# Batt_Op_Amp.net
KiCad netlist of a schematic drawn in Altium Designer
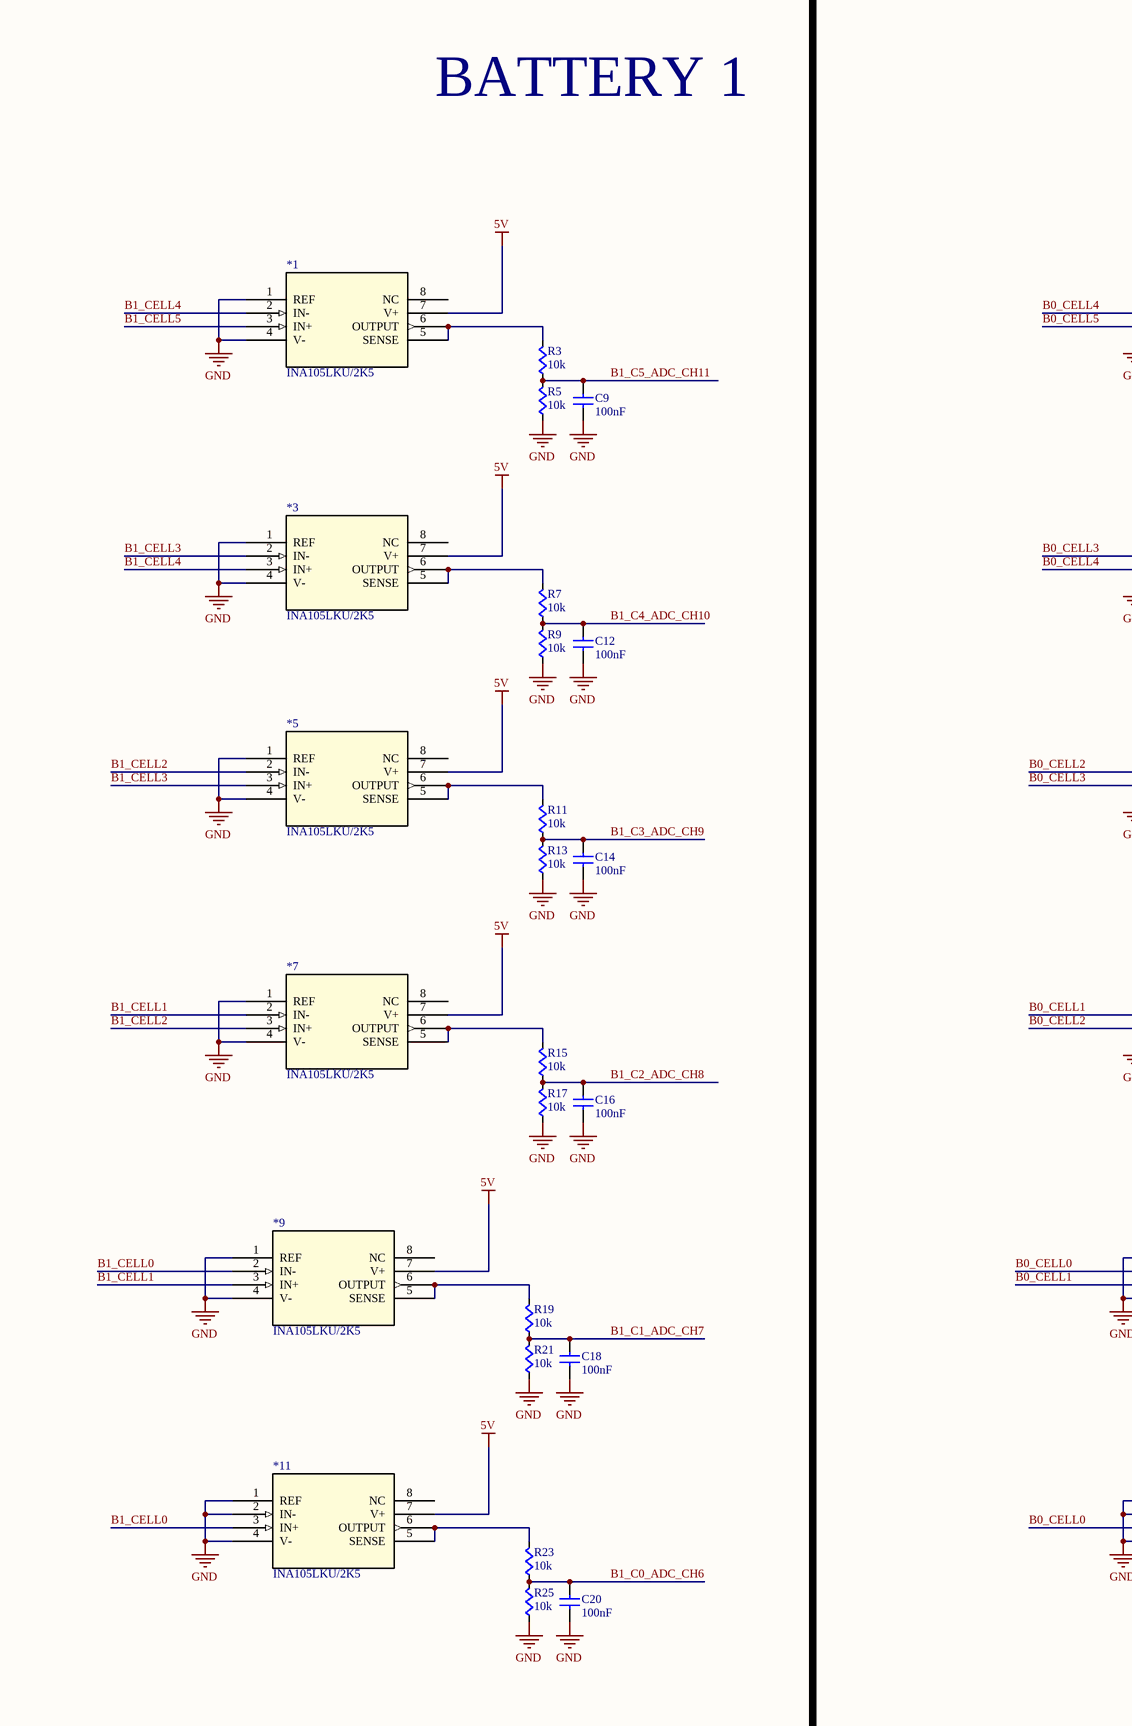
[diagram p0: Batt_Op_Amp.SchDoc, left]
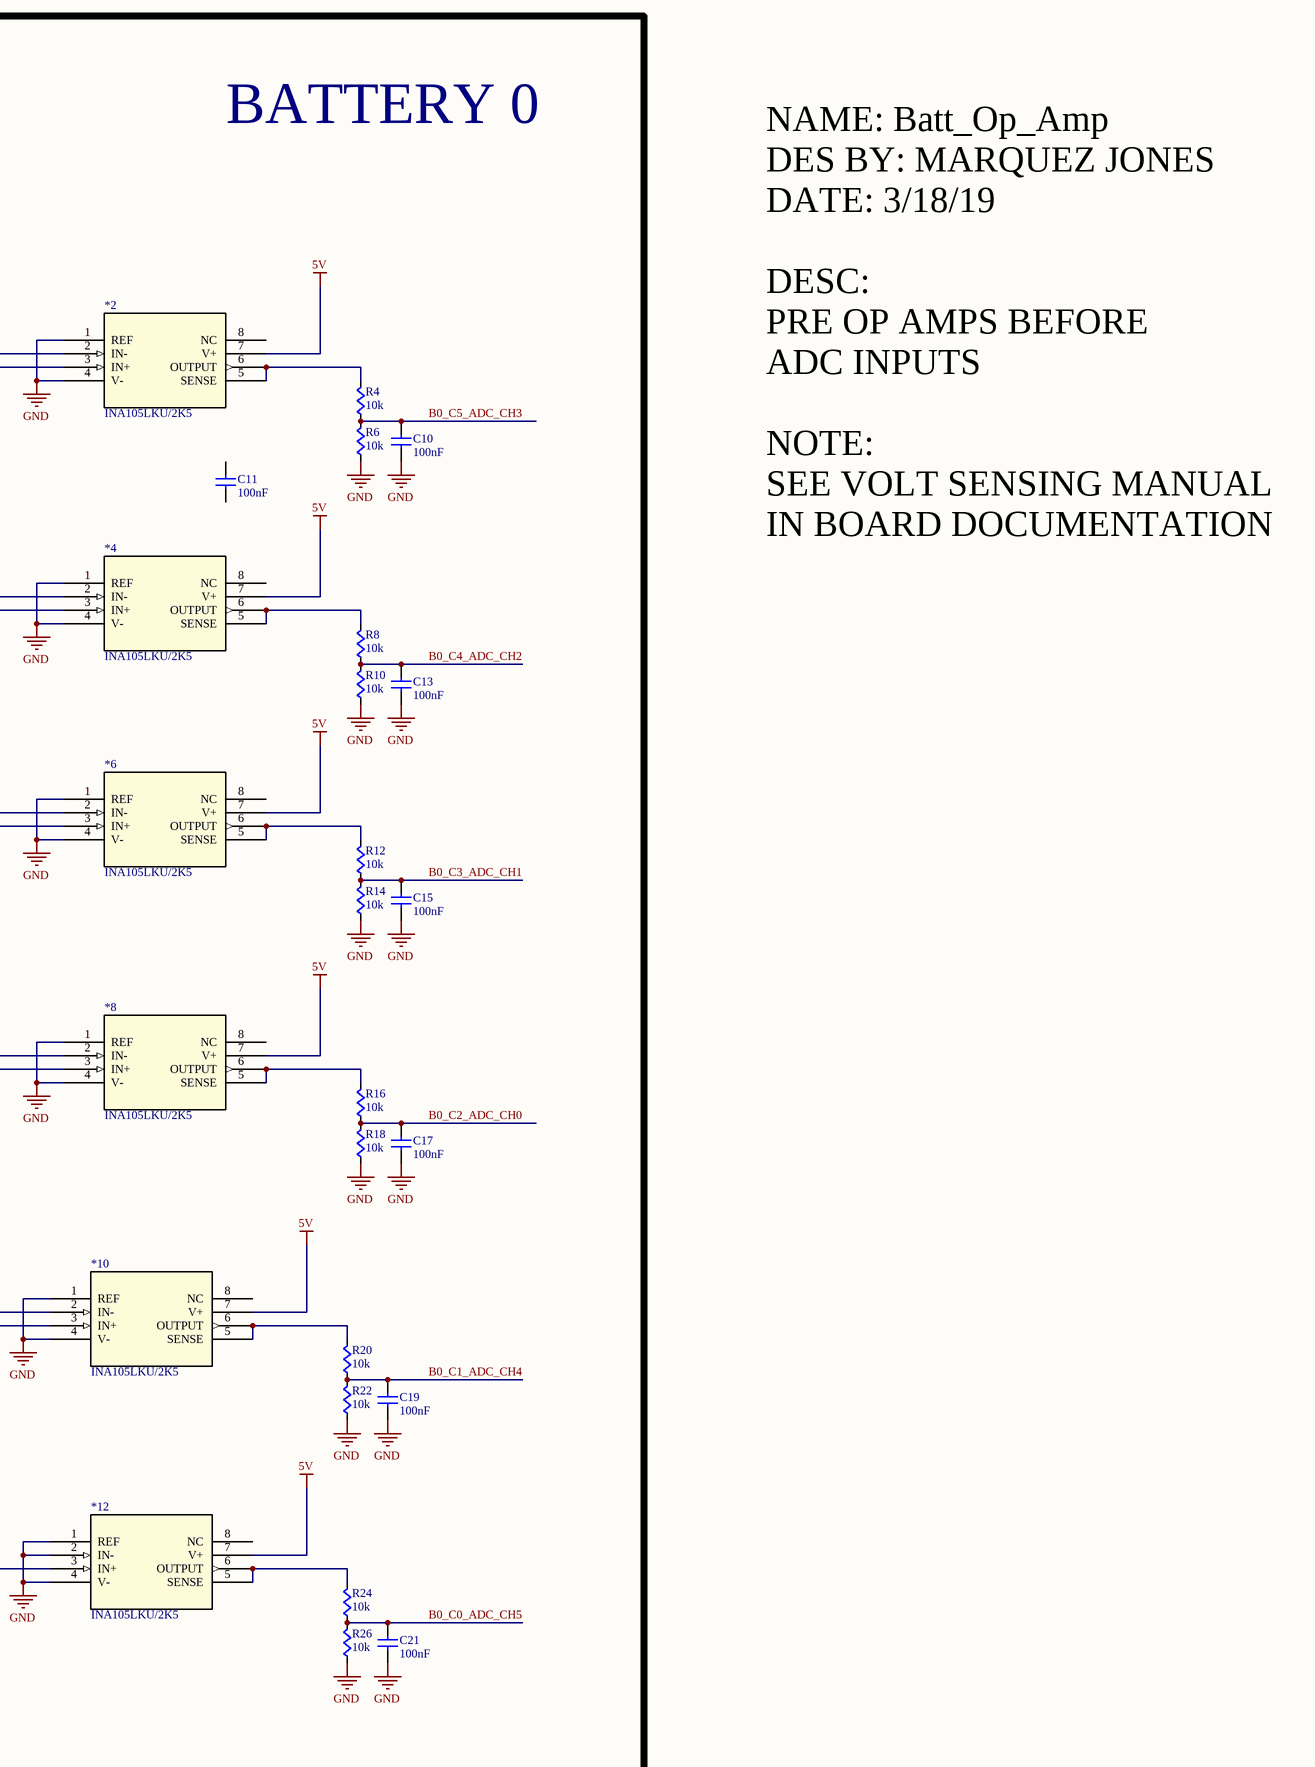
[diagram p1: Batt_Op_Amp.SchDoc, right]

(export (version "E")
  (design (tool "Eeschema 10.0.6"))
  (components
    (comp (ref "*1")
      (value "INA105LKU/2K5")
      (footprint "SOIC-8N")
      (libsource (lib "ICs") (part "INA105LKU/2K5"))
    )
    (comp (ref "*2")
      (value "INA105LKU/2K5")
      (footprint "SOIC-8N")
      (libsource (lib "ICs") (part "INA105LKU/2K5"))
    )
    (comp (ref "*3")
      (value "INA105LKU/2K5")
      (footprint "SOIC-8N")
      (libsource (lib "ICs") (part "INA105LKU/2K5"))
    )
    (comp (ref "*4")
      (value "INA105LKU/2K5")
      (footprint "SOIC-8N")
      (libsource (lib "ICs") (part "INA105LKU/2K5"))
    )
    (comp (ref "*5")
      (value "INA105LKU/2K5")
      (footprint "SOIC-8N")
      (libsource (lib "ICs") (part "INA105LKU/2K5"))
    )
    (comp (ref "*6")
      (value "INA105LKU/2K5")
      (footprint "SOIC-8N")
      (libsource (lib "ICs") (part "INA105LKU/2K5"))
    )
    (comp (ref "*7")
      (value "INA105LKU/2K5")
      (footprint "SOIC-8N")
      (libsource (lib "ICs") (part "INA105LKU/2K5"))
    )
    (comp (ref "*8")
      (value "INA105LKU/2K5")
      (footprint "SOIC-8N")
      (libsource (lib "ICs") (part "INA105LKU/2K5"))
    )
    (comp (ref "*9")
      (value "INA105LKU/2K5")
      (footprint "SOIC-8N")
      (libsource (lib "ICs") (part "INA105LKU/2K5"))
    )
    (comp (ref "*10")
      (value "INA105LKU/2K5")
      (footprint "SOIC-8N")
      (libsource (lib "ICs") (part "INA105LKU/2K5"))
    )
    (comp (ref "*11")
      (value "INA105LKU/2K5")
      (footprint "SOIC-8N")
      (libsource (lib "ICs") (part "INA105LKU/2K5"))
    )
    (comp (ref "*12")
      (value "INA105LKU/2K5")
      (footprint "SOIC-8N")
      (libsource (lib "ICs") (part "INA105LKU/2K5"))
    )
    (comp (ref "C9")
      (value "100nF")
      (footprint "CAPC0603")
      (fields (field (name "Comment") "Cap"))
      (libsource (lib "Passives") (part "Cap"))
    )
    (comp (ref "C10")
      (value "100nF")
      (footprint "CAPC0603")
      (fields (field (name "Comment") "Cap"))
      (libsource (lib "Passives") (part "Cap"))
    )
    (comp (ref "C11")
      (value "100nF")
      (footprint "CAPC0603")
      (fields (field (name "Comment") "Cap"))
      (libsource (lib "Passives") (part "Cap"))
    )
    (comp (ref "C12")
      (value "100nF")
      (footprint "CAPC0603")
      (fields (field (name "Comment") "Cap"))
      (libsource (lib "Passives") (part "Cap"))
    )
    (comp (ref "C13")
      (value "100nF")
      (footprint "CAPC0603")
      (fields (field (name "Comment") "Cap"))
      (libsource (lib "Passives") (part "Cap"))
    )
    (comp (ref "C14")
      (value "100nF")
      (footprint "CAPC0603")
      (fields (field (name "Comment") "Cap"))
      (libsource (lib "Passives") (part "Cap"))
    )
    (comp (ref "C15")
      (value "100nF")
      (footprint "CAPC0603")
      (fields (field (name "Comment") "Cap"))
      (libsource (lib "Passives") (part "Cap"))
    )
    (comp (ref "C16")
      (value "100nF")
      (footprint "CAPC0603")
      (fields (field (name "Comment") "Cap"))
      (libsource (lib "Passives") (part "Cap"))
    )
    (comp (ref "C17")
      (value "100nF")
      (footprint "CAPC0603")
      (fields (field (name "Comment") "Cap"))
      (libsource (lib "Passives") (part "Cap"))
    )
    (comp (ref "C18")
      (value "100nF")
      (footprint "CAPC0603")
      (fields (field (name "Comment") "Cap"))
      (libsource (lib "Passives") (part "Cap"))
    )
    (comp (ref "C19")
      (value "100nF")
      (footprint "CAPC0603")
      (fields (field (name "Comment") "Cap"))
      (libsource (lib "Passives") (part "Cap"))
    )
    (comp (ref "C20")
      (value "100nF")
      (footprint "CAPC0603")
      (fields (field (name "Comment") "Cap"))
      (libsource (lib "Passives") (part "Cap"))
    )
    (comp (ref "C21")
      (value "100nF")
      (footprint "CAPC0603")
      (fields (field (name "Comment") "Cap"))
      (libsource (lib "Passives") (part "Cap"))
    )
    (comp (ref "R3")
      (value "10k")
      (footprint "WSLP5931")
      (fields (field (name "Comment") "Res"))
      (libsource (lib "Passives") (part "Res"))
    )
    (comp (ref "R4")
      (value "10k")
      (footprint "WSLP5931")
      (fields (field (name "Comment") "Res"))
      (libsource (lib "Passives") (part "Res"))
    )
    (comp (ref "R5")
      (value "10k")
      (footprint "WSLP5931")
      (fields (field (name "Comment") "Res"))
      (libsource (lib "Passives") (part "Res"))
    )
    (comp (ref "R6")
      (value "10k")
      (footprint "WSLP5931")
      (fields (field (name "Comment") "Res"))
      (libsource (lib "Passives") (part "Res"))
    )
    (comp (ref "R7")
      (value "10k")
      (footprint "WSLP5931")
      (fields (field (name "Comment") "Res"))
      (libsource (lib "Passives") (part "Res"))
    )
    (comp (ref "R8")
      (value "10k")
      (footprint "WSLP5931")
      (fields (field (name "Comment") "Res"))
      (libsource (lib "Passives") (part "Res"))
    )
    (comp (ref "R9")
      (value "10k")
      (footprint "WSLP5931")
      (fields (field (name "Comment") "Res"))
      (libsource (lib "Passives") (part "Res"))
    )
    (comp (ref "R10")
      (value "10k")
      (footprint "WSLP5931")
      (fields (field (name "Comment") "Res"))
      (libsource (lib "Passives") (part "Res"))
    )
    (comp (ref "R11")
      (value "10k")
      (footprint "WSLP5931")
      (fields (field (name "Comment") "Res"))
      (libsource (lib "Passives") (part "Res"))
    )
    (comp (ref "R12")
      (value "10k")
      (footprint "WSLP5931")
      (fields (field (name "Comment") "Res"))
      (libsource (lib "Passives") (part "Res"))
    )
    (comp (ref "R13")
      (value "10k")
      (footprint "WSLP5931")
      (fields (field (name "Comment") "Res"))
      (libsource (lib "Passives") (part "Res"))
    )
    (comp (ref "R14")
      (value "10k")
      (footprint "WSLP5931")
      (fields (field (name "Comment") "Res"))
      (libsource (lib "Passives") (part "Res"))
    )
    (comp (ref "R15")
      (value "10k")
      (footprint "WSLP5931")
      (fields (field (name "Comment") "Res"))
      (libsource (lib "Passives") (part "Res"))
    )
    (comp (ref "R16")
      (value "10k")
      (footprint "WSLP5931")
      (fields (field (name "Comment") "Res"))
      (libsource (lib "Passives") (part "Res"))
    )
    (comp (ref "R17")
      (value "10k")
      (footprint "WSLP5931")
      (fields (field (name "Comment") "Res"))
      (libsource (lib "Passives") (part "Res"))
    )
    (comp (ref "R18")
      (value "10k")
      (footprint "WSLP5931")
      (fields (field (name "Comment") "Res"))
      (libsource (lib "Passives") (part "Res"))
    )
    (comp (ref "R19")
      (value "10k")
      (footprint "WSLP5931")
      (fields (field (name "Comment") "Res"))
      (libsource (lib "Passives") (part "Res"))
    )
    (comp (ref "R20")
      (value "10k")
      (footprint "WSLP5931")
      (fields (field (name "Comment") "Res"))
      (libsource (lib "Passives") (part "Res"))
    )
    (comp (ref "R21")
      (value "10k")
      (footprint "WSLP5931")
      (fields (field (name "Comment") "Res"))
      (libsource (lib "Passives") (part "Res"))
    )
    (comp (ref "R22")
      (value "10k")
      (footprint "WSLP5931")
      (fields (field (name "Comment") "Res"))
      (libsource (lib "Passives") (part "Res"))
    )
    (comp (ref "R23")
      (value "10k")
      (footprint "WSLP5931")
      (fields (field (name "Comment") "Res"))
      (libsource (lib "Passives") (part "Res"))
    )
    (comp (ref "R24")
      (value "10k")
      (footprint "WSLP5931")
      (fields (field (name "Comment") "Res"))
      (libsource (lib "Passives") (part "Res"))
    )
    (comp (ref "R25")
      (value "10k")
      (footprint "WSLP5931")
      (fields (field (name "Comment") "Res"))
      (libsource (lib "Passives") (part "Res"))
    )
    (comp (ref "R26")
      (value "10k")
      (footprint "WSLP5931")
      (fields (field (name "Comment") "Res"))
      (libsource (lib "Passives") (part "Res"))
    )
  )
  (nets
    (net (code "1") (name "/B0_C0_ADC_CH5") (class "Default")
      (node (ref "C21") (pin "1") (pinfunction "A_1") (pintype "passive"))
      (node (ref "R24") (pin "2") (pinfunction "B_2") (pintype "passive"))
      (node (ref "R26") (pin "1") (pinfunction "A_1") (pintype "passive"))
    )
    (net (code "2") (name "/B0_C1_ADC_CH4") (class "Default")
      (node (ref "C19") (pin "1") (pinfunction "A_1") (pintype "passive"))
      (node (ref "R20") (pin "2") (pinfunction "B_2") (pintype "passive"))
      (node (ref "R22") (pin "1") (pinfunction "A_1") (pintype "passive"))
    )
    (net (code "3") (name "/B0_C2_ADC_CH0") (class "Default")
      (node (ref "C17") (pin "1") (pinfunction "A_1") (pintype "passive"))
      (node (ref "R16") (pin "2") (pinfunction "B_2") (pintype "passive"))
      (node (ref "R18") (pin "1") (pinfunction "A_1") (pintype "passive"))
    )
    (net (code "4") (name "/B0_C3_ADC_CH1") (class "Default")
      (node (ref "C15") (pin "1") (pinfunction "A_1") (pintype "passive"))
      (node (ref "R12") (pin "2") (pinfunction "B_2") (pintype "passive"))
      (node (ref "R14") (pin "1") (pinfunction "A_1") (pintype "passive"))
    )
    (net (code "5") (name "/B0_C4_ADC_CH2") (class "Default")
      (node (ref "C13") (pin "1") (pinfunction "A_1") (pintype "passive"))
      (node (ref "R10") (pin "1") (pinfunction "A_1") (pintype "passive"))
      (node (ref "R8") (pin "2") (pinfunction "B_2") (pintype "passive"))
    )
    (net (code "6") (name "/B0_C5_ADC_CH3") (class "Default")
      (node (ref "C10") (pin "1") (pinfunction "A_1") (pintype "passive"))
      (node (ref "R4") (pin "2") (pinfunction "B_2") (pintype "passive"))
      (node (ref "R6") (pin "1") (pinfunction "A_1") (pintype "passive"))
    )
    (net (code "7") (name "/B0_CELL0") (class "Default")
      (node (ref "*10") (pin "2") (pinfunction "IN-_2") (pintype "input"))
      (node (ref "*12") (pin "3") (pinfunction "IN+_3") (pintype "input"))
    )
    (net (code "8") (name "/B0_CELL1") (class "Default")
      (node (ref "*10") (pin "3") (pinfunction "IN+_3") (pintype "input"))
      (node (ref "*8") (pin "2") (pinfunction "IN-_2") (pintype "input"))
    )
    (net (code "9") (name "/B0_CELL2") (class "Default")
      (node (ref "*6") (pin "2") (pinfunction "IN-_2") (pintype "input"))
      (node (ref "*8") (pin "3") (pinfunction "IN+_3") (pintype "input"))
    )
    (net (code "10") (name "/B0_CELL3") (class "Default")
      (node (ref "*4") (pin "2") (pinfunction "IN-_2") (pintype "input"))
      (node (ref "*6") (pin "3") (pinfunction "IN+_3") (pintype "input"))
    )
    (net (code "11") (name "/B0_CELL4") (class "Default")
      (node (ref "*2") (pin "2") (pinfunction "IN-_2") (pintype "input"))
      (node (ref "*4") (pin "3") (pinfunction "IN+_3") (pintype "input"))
    )
    (net (code "12") (name "/B0_CELL5") (class "Default")
      (node (ref "*2") (pin "3") (pinfunction "IN+_3") (pintype "input"))
    )
    (net (code "13") (name "/B1_C0_ADC_CH6") (class "Default")
      (node (ref "C20") (pin "1") (pinfunction "A_1") (pintype "passive"))
      (node (ref "R23") (pin "2") (pinfunction "B_2") (pintype "passive"))
      (node (ref "R25") (pin "1") (pinfunction "A_1") (pintype "passive"))
    )
    (net (code "14") (name "/B1_C1_ADC_CH7") (class "Default")
      (node (ref "C18") (pin "1") (pinfunction "A_1") (pintype "passive"))
      (node (ref "R19") (pin "2") (pinfunction "B_2") (pintype "passive"))
      (node (ref "R21") (pin "1") (pinfunction "A_1") (pintype "passive"))
    )
    (net (code "15") (name "/B1_C2_ADC_CH8") (class "Default")
      (node (ref "C16") (pin "1") (pinfunction "A_1") (pintype "passive"))
      (node (ref "R15") (pin "2") (pinfunction "B_2") (pintype "passive"))
      (node (ref "R17") (pin "1") (pinfunction "A_1") (pintype "passive"))
    )
    (net (code "16") (name "/B1_C3_ADC_CH9") (class "Default")
      (node (ref "C14") (pin "1") (pinfunction "A_1") (pintype "passive"))
      (node (ref "R11") (pin "2") (pinfunction "B_2") (pintype "passive"))
      (node (ref "R13") (pin "1") (pinfunction "A_1") (pintype "passive"))
    )
    (net (code "17") (name "/B1_C4_ADC_CH10") (class "Default")
      (node (ref "C12") (pin "1") (pinfunction "A_1") (pintype "passive"))
      (node (ref "R7") (pin "2") (pinfunction "B_2") (pintype "passive"))
      (node (ref "R9") (pin "1") (pinfunction "A_1") (pintype "passive"))
    )
    (net (code "18") (name "/B1_C5_ADC_CH11") (class "Default")
      (node (ref "C9") (pin "1") (pinfunction "A_1") (pintype "passive"))
      (node (ref "R3") (pin "2") (pinfunction "B_2") (pintype "passive"))
      (node (ref "R5") (pin "1") (pinfunction "A_1") (pintype "passive"))
    )
    (net (code "19") (name "/B1_CELL0") (class "Default")
      (node (ref "*11") (pin "3") (pinfunction "IN+_3") (pintype "input"))
      (node (ref "*9") (pin "2") (pinfunction "IN-_2") (pintype "input"))
    )
    (net (code "20") (name "/B1_CELL1") (class "Default")
      (node (ref "*7") (pin "2") (pinfunction "IN-_2") (pintype "input"))
      (node (ref "*9") (pin "3") (pinfunction "IN+_3") (pintype "input"))
    )
    (net (code "21") (name "/B1_CELL2") (class "Default")
      (node (ref "*5") (pin "2") (pinfunction "IN-_2") (pintype "input"))
      (node (ref "*7") (pin "3") (pinfunction "IN+_3") (pintype "input"))
    )
    (net (code "22") (name "/B1_CELL3") (class "Default")
      (node (ref "*3") (pin "2") (pinfunction "IN-_2") (pintype "input"))
      (node (ref "*5") (pin "3") (pinfunction "IN+_3") (pintype "input"))
    )
    (net (code "23") (name "/B1_CELL4") (class "Default")
      (node (ref "*1") (pin "2") (pinfunction "IN-_2") (pintype "input"))
      (node (ref "*3") (pin "3") (pinfunction "IN+_3") (pintype "input"))
    )
    (net (code "24") (name "/B1_CELL5") (class "Default")
      (node (ref "*1") (pin "3") (pinfunction "IN+_3") (pintype "input"))
    )
    (net (code "25") (name "5V") (class "Default")
      (node (ref "*1") (pin "7") (pinfunction "V+_7") (pintype "power_in"))
      (node (ref "*10") (pin "7") (pinfunction "V+_7") (pintype "power_in"))
      (node (ref "*11") (pin "7") (pinfunction "V+_7") (pintype "power_in"))
      (node (ref "*12") (pin "7") (pinfunction "V+_7") (pintype "power_in"))
      (node (ref "*2") (pin "7") (pinfunction "V+_7") (pintype "power_in"))
      (node (ref "*3") (pin "7") (pinfunction "V+_7") (pintype "power_in"))
      (node (ref "*4") (pin "7") (pinfunction "V+_7") (pintype "power_in"))
      (node (ref "*5") (pin "7") (pinfunction "V+_7") (pintype "power_in"))
      (node (ref "*6") (pin "7") (pinfunction "V+_7") (pintype "power_in"))
      (node (ref "*7") (pin "7") (pinfunction "V+_7") (pintype "power_in"))
      (node (ref "*8") (pin "7") (pinfunction "V+_7") (pintype "power_in"))
      (node (ref "*9") (pin "7") (pinfunction "V+_7") (pintype "power_in"))
    )
    (net (code "26") (name "GND") (class "Default")
      (node (ref "*1") (pin "1") (pinfunction "REF_1") (pintype "power_in"))
      (node (ref "*1") (pin "4") (pinfunction "V-_4") (pintype "power_in"))
      (node (ref "*10") (pin "1") (pinfunction "REF_1") (pintype "power_in"))
      (node (ref "*10") (pin "4") (pinfunction "V-_4") (pintype "power_in"))
      (node (ref "*11") (pin "1") (pinfunction "REF_1") (pintype "power_in"))
      (node (ref "*11") (pin "2") (pinfunction "IN-_2") (pintype "input"))
      (node (ref "*11") (pin "4") (pinfunction "V-_4") (pintype "power_in"))
      (node (ref "*12") (pin "1") (pinfunction "REF_1") (pintype "power_in"))
      (node (ref "*12") (pin "2") (pinfunction "IN-_2") (pintype "input"))
      (node (ref "*12") (pin "4") (pinfunction "V-_4") (pintype "power_in"))
      (node (ref "*2") (pin "1") (pinfunction "REF_1") (pintype "power_in"))
      (node (ref "*2") (pin "4") (pinfunction "V-_4") (pintype "power_in"))
      (node (ref "*3") (pin "1") (pinfunction "REF_1") (pintype "power_in"))
      (node (ref "*3") (pin "4") (pinfunction "V-_4") (pintype "power_in"))
      (node (ref "*4") (pin "1") (pinfunction "REF_1") (pintype "power_in"))
      (node (ref "*4") (pin "4") (pinfunction "V-_4") (pintype "power_in"))
      (node (ref "*5") (pin "1") (pinfunction "REF_1") (pintype "power_in"))
      (node (ref "*5") (pin "4") (pinfunction "V-_4") (pintype "power_in"))
      (node (ref "*6") (pin "1") (pinfunction "REF_1") (pintype "power_in"))
      (node (ref "*6") (pin "4") (pinfunction "V-_4") (pintype "power_in"))
      (node (ref "*7") (pin "1") (pinfunction "REF_1") (pintype "power_in"))
      (node (ref "*7") (pin "4") (pinfunction "V-_4") (pintype "power_in"))
      (node (ref "*8") (pin "1") (pinfunction "REF_1") (pintype "power_in"))
      (node (ref "*8") (pin "4") (pinfunction "V-_4") (pintype "power_in"))
      (node (ref "*9") (pin "1") (pinfunction "REF_1") (pintype "power_in"))
      (node (ref "*9") (pin "4") (pinfunction "V-_4") (pintype "power_in"))
      (node (ref "C10") (pin "2") (pinfunction "B_2") (pintype "passive"))
      (node (ref "C12") (pin "2") (pinfunction "B_2") (pintype "passive"))
      (node (ref "C13") (pin "2") (pinfunction "B_2") (pintype "passive"))
      (node (ref "C14") (pin "2") (pinfunction "B_2") (pintype "passive"))
      (node (ref "C15") (pin "2") (pinfunction "B_2") (pintype "passive"))
      (node (ref "C16") (pin "2") (pinfunction "B_2") (pintype "passive"))
      (node (ref "C17") (pin "2") (pinfunction "B_2") (pintype "passive"))
      (node (ref "C18") (pin "2") (pinfunction "B_2") (pintype "passive"))
      (node (ref "C19") (pin "2") (pinfunction "B_2") (pintype "passive"))
      (node (ref "C20") (pin "2") (pinfunction "B_2") (pintype "passive"))
      (node (ref "C21") (pin "2") (pinfunction "B_2") (pintype "passive"))
      (node (ref "C9") (pin "2") (pinfunction "B_2") (pintype "passive"))
      (node (ref "R10") (pin "2") (pinfunction "B_2") (pintype "passive"))
      (node (ref "R13") (pin "2") (pinfunction "B_2") (pintype "passive"))
      (node (ref "R14") (pin "2") (pinfunction "B_2") (pintype "passive"))
      (node (ref "R17") (pin "2") (pinfunction "B_2") (pintype "passive"))
      (node (ref "R18") (pin "2") (pinfunction "B_2") (pintype "passive"))
      (node (ref "R21") (pin "2") (pinfunction "B_2") (pintype "passive"))
      (node (ref "R22") (pin "2") (pinfunction "B_2") (pintype "passive"))
      (node (ref "R25") (pin "2") (pinfunction "B_2") (pintype "passive"))
      (node (ref "R26") (pin "2") (pinfunction "B_2") (pintype "passive"))
      (node (ref "R5") (pin "2") (pinfunction "B_2") (pintype "passive"))
      (node (ref "R6") (pin "2") (pinfunction "B_2") (pintype "passive"))
      (node (ref "R9") (pin "2") (pinfunction "B_2") (pintype "passive"))
    )
    (net (code "27") (name "Net-(*1-OUTPUT)") (class "Default")
      (node (ref "*1") (pin "5") (pinfunction "SENSE_5") (pintype "passive"))
      (node (ref "*1") (pin "6") (pinfunction "OUTPUT_6") (pintype "output"))
      (node (ref "R3") (pin "1") (pinfunction "A_1") (pintype "passive"))
    )
    (net (code "28") (name "Net-(*2-OUTPUT)") (class "Default")
      (node (ref "*2") (pin "5") (pinfunction "SENSE_5") (pintype "passive"))
      (node (ref "*2") (pin "6") (pinfunction "OUTPUT_6") (pintype "output"))
      (node (ref "R4") (pin "1") (pinfunction "A_1") (pintype "passive"))
    )
    (net (code "29") (name "Net-(*3-OUTPUT)") (class "Default")
      (node (ref "*3") (pin "5") (pinfunction "SENSE_5") (pintype "passive"))
      (node (ref "*3") (pin "6") (pinfunction "OUTPUT_6") (pintype "output"))
      (node (ref "R7") (pin "1") (pinfunction "A_1") (pintype "passive"))
    )
    (net (code "30") (name "Net-(*4-OUTPUT)") (class "Default")
      (node (ref "*4") (pin "5") (pinfunction "SENSE_5") (pintype "passive"))
      (node (ref "*4") (pin "6") (pinfunction "OUTPUT_6") (pintype "output"))
      (node (ref "R8") (pin "1") (pinfunction "A_1") (pintype "passive"))
    )
    (net (code "31") (name "Net-(*5-OUTPUT)") (class "Default")
      (node (ref "*5") (pin "5") (pinfunction "SENSE_5") (pintype "passive"))
      (node (ref "*5") (pin "6") (pinfunction "OUTPUT_6") (pintype "output"))
      (node (ref "R11") (pin "1") (pinfunction "A_1") (pintype "passive"))
    )
    (net (code "32") (name "Net-(*6-OUTPUT)") (class "Default")
      (node (ref "*6") (pin "5") (pinfunction "SENSE_5") (pintype "passive"))
      (node (ref "*6") (pin "6") (pinfunction "OUTPUT_6") (pintype "output"))
      (node (ref "R12") (pin "1") (pinfunction "A_1") (pintype "passive"))
    )
    (net (code "33") (name "Net-(*7-OUTPUT)") (class "Default")
      (node (ref "*7") (pin "5") (pinfunction "SENSE_5") (pintype "passive"))
      (node (ref "*7") (pin "6") (pinfunction "OUTPUT_6") (pintype "output"))
      (node (ref "R15") (pin "1") (pinfunction "A_1") (pintype "passive"))
    )
    (net (code "34") (name "Net-(*8-OUTPUT)") (class "Default")
      (node (ref "*8") (pin "5") (pinfunction "SENSE_5") (pintype "passive"))
      (node (ref "*8") (pin "6") (pinfunction "OUTPUT_6") (pintype "output"))
      (node (ref "R16") (pin "1") (pinfunction "A_1") (pintype "passive"))
    )
    (net (code "35") (name "Net-(*9-OUTPUT)") (class "Default")
      (node (ref "*9") (pin "5") (pinfunction "SENSE_5") (pintype "passive"))
      (node (ref "*9") (pin "6") (pinfunction "OUTPUT_6") (pintype "output"))
      (node (ref "R19") (pin "1") (pinfunction "A_1") (pintype "passive"))
    )
    (net (code "36") (name "Net-(*10-OUTPUT)") (class "Default")
      (node (ref "*10") (pin "5") (pinfunction "SENSE_5") (pintype "passive"))
      (node (ref "*10") (pin "6") (pinfunction "OUTPUT_6") (pintype "output"))
      (node (ref "R20") (pin "1") (pinfunction "A_1") (pintype "passive"))
    )
    (net (code "37") (name "Net-(*11-OUTPUT)") (class "Default")
      (node (ref "*11") (pin "5") (pinfunction "SENSE_5") (pintype "passive"))
      (node (ref "*11") (pin "6") (pinfunction "OUTPUT_6") (pintype "output"))
      (node (ref "R23") (pin "1") (pinfunction "A_1") (pintype "passive"))
    )
    (net (code "38") (name "Net-(*12-OUTPUT)") (class "Default")
      (node (ref "*12") (pin "5") (pinfunction "SENSE_5") (pintype "passive"))
      (node (ref "*12") (pin "6") (pinfunction "OUTPUT_6") (pintype "output"))
      (node (ref "R24") (pin "1") (pinfunction "A_1") (pintype "passive"))
    )
    (net (code "39") (name "unconnected-(*1-NC-Pad8)") (class "Default")
      (node (ref "*1") (pin "8") (pinfunction "NC_8") (pintype "passive"))
    )
    (net (code "40") (name "unconnected-(*2-NC-Pad8)") (class "Default")
      (node (ref "*2") (pin "8") (pinfunction "NC_8") (pintype "passive"))
    )
    (net (code "41") (name "unconnected-(*3-NC-Pad8)") (class "Default")
      (node (ref "*3") (pin "8") (pinfunction "NC_8") (pintype "passive"))
    )
    (net (code "42") (name "unconnected-(*4-NC-Pad8)") (class "Default")
      (node (ref "*4") (pin "8") (pinfunction "NC_8") (pintype "passive"))
    )
    (net (code "43") (name "unconnected-(*5-NC-Pad8)") (class "Default")
      (node (ref "*5") (pin "8") (pinfunction "NC_8") (pintype "passive"))
    )
    (net (code "44") (name "unconnected-(*6-NC-Pad8)") (class "Default")
      (node (ref "*6") (pin "8") (pinfunction "NC_8") (pintype "passive"))
    )
    (net (code "45") (name "unconnected-(*7-NC-Pad8)") (class "Default")
      (node (ref "*7") (pin "8") (pinfunction "NC_8") (pintype "passive"))
    )
    (net (code "46") (name "unconnected-(*8-NC-Pad8)") (class "Default")
      (node (ref "*8") (pin "8") (pinfunction "NC_8") (pintype "passive"))
    )
    (net (code "47") (name "unconnected-(*9-NC-Pad8)") (class "Default")
      (node (ref "*9") (pin "8") (pinfunction "NC_8") (pintype "passive"))
    )
    (net (code "48") (name "unconnected-(*10-NC-Pad8)") (class "Default")
      (node (ref "*10") (pin "8") (pinfunction "NC_8") (pintype "passive"))
    )
    (net (code "49") (name "unconnected-(*11-NC-Pad8)") (class "Default")
      (node (ref "*11") (pin "8") (pinfunction "NC_8") (pintype "passive"))
    )
    (net (code "50") (name "unconnected-(*12-NC-Pad8)") (class "Default")
      (node (ref "*12") (pin "8") (pinfunction "NC_8") (pintype "passive"))
    )
    (net (code "51") (name "unconnected-(C11-A-Pad1)") (class "Default")
      (node (ref "C11") (pin "1") (pinfunction "A_1") (pintype "passive"))
    )
    (net (code "52") (name "unconnected-(C11-B-Pad2)") (class "Default")
      (node (ref "C11") (pin "2") (pinfunction "B_2") (pintype "passive"))
    )
  )
)
